# Display.net
KiCad netlist of a schematic drawn in EAGLE
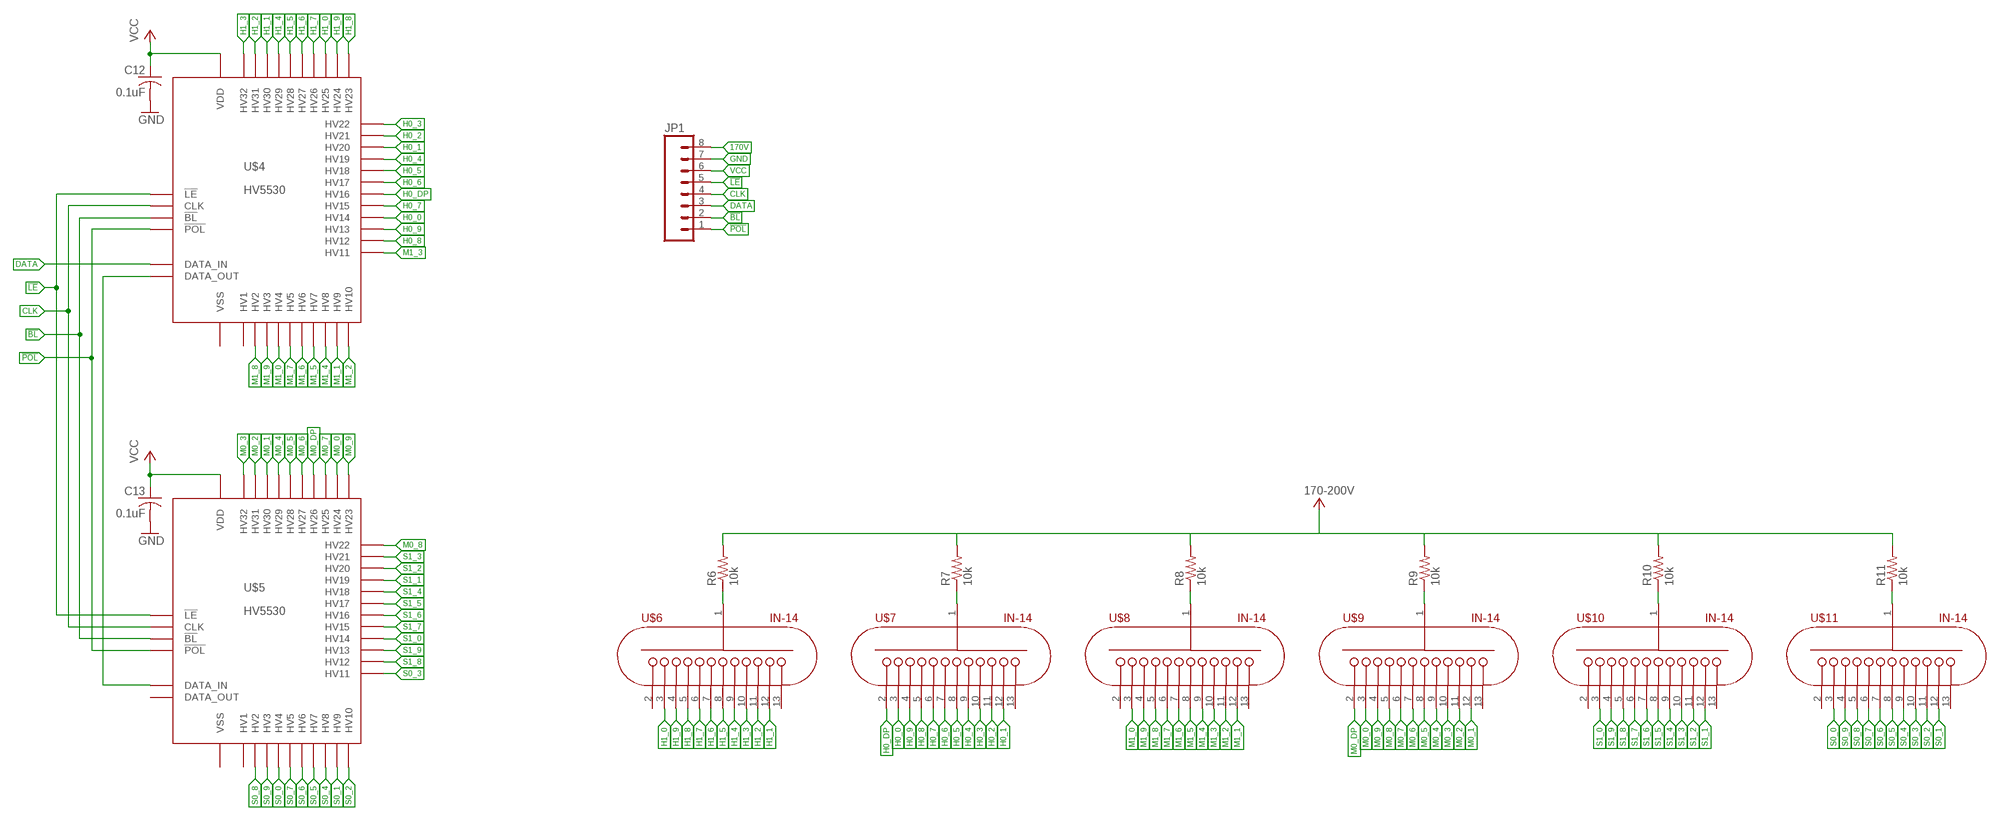
[diagram p0: schematic, sheet 1]

(export (version "E")
  (design (tool "Eeschema 10.0.6"))
  (components
    (comp (ref "C12")
      (value "0.1uF")
      (footprint "eagle-import:C0603")
      (libsource (lib "eagle-import") (part "C-USC0603"))
    )
    (comp (ref "C13")
      (value "0.1uF")
      (footprint "eagle-import:C0603")
      (libsource (lib "eagle-import") (part "C-USC0603"))
    )
    (comp (ref "JP1")
      (value "M08")
      (footprint "eagle-import:1X08_PIN1_NO_SILK")
      (libsource (lib "eagle-import") (part "M08"))
    )
    (comp (ref "R6")
      (value "10k")
      (footprint "eagle-import:R0603")
      (libsource (lib "eagle-import") (part "R-US_R0603"))
    )
    (comp (ref "R7")
      (value "10k")
      (footprint "eagle-import:R0603")
      (libsource (lib "eagle-import") (part "R-US_R0603"))
    )
    (comp (ref "R8")
      (value "10k")
      (footprint "eagle-import:R0603")
      (libsource (lib "eagle-import") (part "R-US_R0603"))
    )
    (comp (ref "R9")
      (value "10k")
      (footprint "eagle-import:R0603")
      (libsource (lib "eagle-import") (part "R-US_R0603"))
    )
    (comp (ref "R10")
      (value "10k")
      (footprint "eagle-import:R0603")
      (libsource (lib "eagle-import") (part "R-US_R0603"))
    )
    (comp (ref "R11")
      (value "10k")
      (footprint "eagle-import:R0603")
      (libsource (lib "eagle-import") (part "R-US_R0603"))
    )
    (comp (ref "U$4")
      (value "HV5530PLCC")
      (footprint "eagle-import:PLCC")
      (libsource (lib "eagle-import") (part "HV5530PLCC"))
    )
    (comp (ref "U$5")
      (value "HV5530PLCC")
      (footprint "eagle-import:PLCC")
      (libsource (lib "eagle-import") (part "HV5530PLCC"))
    )
    (comp (ref "U$6")
      (value "IN-14")
      (footprint "eagle-import:IN-14")
      (libsource (lib "eagle-import") (part "IN-14"))
    )
    (comp (ref "U$7")
      (value "IN-14")
      (footprint "eagle-import:IN-14")
      (libsource (lib "eagle-import") (part "IN-14"))
    )
    (comp (ref "U$8")
      (value "IN-14")
      (footprint "eagle-import:IN-14")
      (libsource (lib "eagle-import") (part "IN-14"))
    )
    (comp (ref "U$9")
      (value "IN-14")
      (footprint "eagle-import:IN-14")
      (libsource (lib "eagle-import") (part "IN-14"))
    )
    (comp (ref "U$10")
      (value "IN-14")
      (footprint "eagle-import:IN-14")
      (libsource (lib "eagle-import") (part "IN-14"))
    )
    (comp (ref "U$11")
      (value "IN-14")
      (footprint "eagle-import:IN-14")
      (libsource (lib "eagle-import") (part "IN-14"))
    )
  )
  (nets
    (net (code "1") (name "/~{BL}") (class "Default")
      (node (ref "JP1") (pin "2") (pinfunction "2_2") (pintype "passive"))
      (node (ref "U$4") (pin "BL") (pinfunction "~{BL}_BL") (pintype "bidirectional"))
      (node (ref "U$5") (pin "BL") (pinfunction "~{BL}_BL") (pintype "bidirectional"))
    )
    (net (code "2") (name "/~{LE}") (class "Default")
      (node (ref "JP1") (pin "5") (pinfunction "5_5") (pintype "passive"))
      (node (ref "U$4") (pin "LE") (pinfunction "~{LE}_LE") (pintype "bidirectional"))
      (node (ref "U$5") (pin "LE") (pinfunction "~{LE}_LE") (pintype "bidirectional"))
    )
    (net (code "3") (name "/~{POL}") (class "Default")
      (node (ref "JP1") (pin "1") (pinfunction "1_1") (pintype "passive"))
      (node (ref "U$4") (pin "POL") (pinfunction "~{POL}_POL") (pintype "bidirectional"))
      (node (ref "U$5") (pin "POL") (pinfunction "~{POL}_POL") (pintype "bidirectional"))
    )
    (net (code "4") (name "170V") (class "Default")
      (node (ref "JP1") (pin "8") (pinfunction "8_8") (pintype "passive"))
      (node (ref "R10") (pin "2") (pinfunction "2_2") (pintype "passive"))
      (node (ref "R11") (pin "2") (pinfunction "2_2") (pintype "passive"))
      (node (ref "R6") (pin "2") (pinfunction "2_2") (pintype "passive"))
      (node (ref "R7") (pin "2") (pinfunction "2_2") (pintype "passive"))
      (node (ref "R8") (pin "2") (pinfunction "2_2") (pintype "passive"))
      (node (ref "R9") (pin "2") (pinfunction "2_2") (pintype "passive"))
    )
    (net (code "5") (name "CLK") (class "Default")
      (node (ref "JP1") (pin "4") (pinfunction "4_4") (pintype "passive"))
      (node (ref "U$4") (pin "CLK") (pinfunction "CLK_CLK") (pintype "bidirectional"))
      (node (ref "U$5") (pin "CLK") (pinfunction "CLK_CLK") (pintype "bidirectional"))
    )
    (net (code "6") (name "DATA") (class "Default")
      (node (ref "JP1") (pin "3") (pinfunction "3_3") (pintype "passive"))
      (node (ref "U$4") (pin "D_IN") (pinfunction "DATA_IN_D_IN") (pintype "bidirectional"))
    )
    (net (code "7") (name "GND") (class "Default")
      (node (ref "C12") (pin "2") (pinfunction "2_2") (pintype "passive"))
      (node (ref "C13") (pin "2") (pinfunction "2_2") (pintype "passive"))
      (node (ref "JP1") (pin "7") (pinfunction "7_7") (pintype "passive"))
    )
    (net (code "8") (name "H0_0") (class "Default")
      (node (ref "U$4") (pin "HV14") (pinfunction "HV14_HV14") (pintype "bidirectional"))
      (node (ref "U$7") (pin "3") (pinfunction "P$3_3") (pintype "bidirectional"))
    )
    (net (code "9") (name "H0_1") (class "Default")
      (node (ref "U$4") (pin "HV20") (pinfunction "HV20_HV20") (pintype "bidirectional"))
      (node (ref "U$7") (pin "12") (pinfunction "P$12_12") (pintype "bidirectional"))
    )
    (net (code "10") (name "H0_2") (class "Default")
      (node (ref "U$4") (pin "HV21") (pinfunction "HV21_HV21") (pintype "bidirectional"))
      (node (ref "U$7") (pin "11") (pinfunction "P$11_11") (pintype "bidirectional"))
    )
    (net (code "11") (name "H0_3") (class "Default")
      (node (ref "U$4") (pin "HV22") (pinfunction "HV22_HV22") (pintype "bidirectional"))
      (node (ref "U$7") (pin "10") (pinfunction "P$10_10") (pintype "bidirectional"))
    )
    (net (code "12") (name "H0_4") (class "Default")
      (node (ref "U$4") (pin "HV19") (pinfunction "HV19_HV19") (pintype "bidirectional"))
      (node (ref "U$7") (pin "9") (pinfunction "P$9_9") (pintype "bidirectional"))
    )
    (net (code "13") (name "H0_5") (class "Default")
      (node (ref "U$4") (pin "HV18") (pinfunction "HV18_HV18") (pintype "bidirectional"))
      (node (ref "U$7") (pin "8") (pinfunction "P$8_8") (pintype "bidirectional"))
    )
    (net (code "14") (name "H0_6") (class "Default")
      (node (ref "U$4") (pin "HV17") (pinfunction "HV17_HV17") (pintype "bidirectional"))
      (node (ref "U$7") (pin "7") (pinfunction "P$7_7") (pintype "bidirectional"))
    )
    (net (code "15") (name "H0_7") (class "Default")
      (node (ref "U$4") (pin "HV15") (pinfunction "HV15_HV15") (pintype "bidirectional"))
      (node (ref "U$7") (pin "6") (pinfunction "P$6_6") (pintype "bidirectional"))
    )
    (net (code "16") (name "H0_8") (class "Default")
      (node (ref "U$4") (pin "HV12") (pinfunction "HV12_HV12") (pintype "bidirectional"))
      (node (ref "U$7") (pin "5") (pinfunction "P$5_5") (pintype "bidirectional"))
    )
    (net (code "17") (name "H0_9") (class "Default")
      (node (ref "U$4") (pin "HV13") (pinfunction "HV13_HV13") (pintype "bidirectional"))
      (node (ref "U$7") (pin "4") (pinfunction "P$4_4") (pintype "bidirectional"))
    )
    (net (code "18") (name "H0_DP") (class "Default")
      (node (ref "U$4") (pin "HV16") (pinfunction "HV16_HV16") (pintype "bidirectional"))
      (node (ref "U$7") (pin "2") (pinfunction "P$2_2") (pintype "bidirectional"))
    )
    (net (code "19") (name "H1_0") (class "Default")
      (node (ref "U$4") (pin "HV25") (pinfunction "HV25_HV25") (pintype "bidirectional"))
      (node (ref "U$6") (pin "3") (pinfunction "P$3_3") (pintype "bidirectional"))
    )
    (net (code "20") (name "H1_1") (class "Default")
      (node (ref "U$4") (pin "HV30") (pinfunction "HV30_HV30") (pintype "bidirectional"))
      (node (ref "U$6") (pin "12") (pinfunction "P$12_12") (pintype "bidirectional"))
    )
    (net (code "21") (name "H1_2") (class "Default")
      (node (ref "U$4") (pin "HV31") (pinfunction "HV31_HV31") (pintype "bidirectional"))
      (node (ref "U$6") (pin "11") (pinfunction "P$11_11") (pintype "bidirectional"))
    )
    (net (code "22") (name "H1_3") (class "Default")
      (node (ref "U$4") (pin "HV32") (pinfunction "HV32_HV32") (pintype "bidirectional"))
      (node (ref "U$6") (pin "10") (pinfunction "P$10_10") (pintype "bidirectional"))
    )
    (net (code "23") (name "H1_4") (class "Default")
      (node (ref "U$4") (pin "HV29") (pinfunction "HV29_HV29") (pintype "bidirectional"))
      (node (ref "U$6") (pin "9") (pinfunction "P$9_9") (pintype "bidirectional"))
    )
    (net (code "24") (name "H1_5") (class "Default")
      (node (ref "U$4") (pin "HV28") (pinfunction "HV28_HV28") (pintype "bidirectional"))
      (node (ref "U$6") (pin "8") (pinfunction "P$8_8") (pintype "bidirectional"))
    )
    (net (code "25") (name "H1_6") (class "Default")
      (node (ref "U$4") (pin "HV27") (pinfunction "HV27_HV27") (pintype "bidirectional"))
      (node (ref "U$6") (pin "7") (pinfunction "P$7_7") (pintype "bidirectional"))
    )
    (net (code "26") (name "H1_7") (class "Default")
      (node (ref "U$4") (pin "HV26") (pinfunction "HV26_HV26") (pintype "bidirectional"))
      (node (ref "U$6") (pin "6") (pinfunction "P$6_6") (pintype "bidirectional"))
    )
    (net (code "27") (name "H1_8") (class "Default")
      (node (ref "U$4") (pin "HV23") (pinfunction "HV23_HV23") (pintype "bidirectional"))
      (node (ref "U$6") (pin "5") (pinfunction "P$5_5") (pintype "bidirectional"))
    )
    (net (code "28") (name "H1_9") (class "Default")
      (node (ref "U$4") (pin "HV24") (pinfunction "HV24_HV24") (pintype "bidirectional"))
      (node (ref "U$6") (pin "4") (pinfunction "P$4_4") (pintype "bidirectional"))
    )
    (net (code "29") (name "M0_0") (class "Default")
      (node (ref "U$5") (pin "HV24") (pinfunction "HV24_HV24") (pintype "bidirectional"))
      (node (ref "U$9") (pin "3") (pinfunction "P$3_3") (pintype "bidirectional"))
    )
    (net (code "30") (name "M0_1") (class "Default")
      (node (ref "U$5") (pin "HV30") (pinfunction "HV30_HV30") (pintype "bidirectional"))
      (node (ref "U$9") (pin "12") (pinfunction "P$12_12") (pintype "bidirectional"))
    )
    (net (code "31") (name "M0_2") (class "Default")
      (node (ref "U$5") (pin "HV31") (pinfunction "HV31_HV31") (pintype "bidirectional"))
      (node (ref "U$9") (pin "11") (pinfunction "P$11_11") (pintype "bidirectional"))
    )
    (net (code "32") (name "M0_3") (class "Default")
      (node (ref "U$5") (pin "HV32") (pinfunction "HV32_HV32") (pintype "bidirectional"))
      (node (ref "U$9") (pin "10") (pinfunction "P$10_10") (pintype "bidirectional"))
    )
    (net (code "33") (name "M0_4") (class "Default")
      (node (ref "U$5") (pin "HV29") (pinfunction "HV29_HV29") (pintype "bidirectional"))
      (node (ref "U$9") (pin "9") (pinfunction "P$9_9") (pintype "bidirectional"))
    )
    (net (code "34") (name "M0_5") (class "Default")
      (node (ref "U$5") (pin "HV28") (pinfunction "HV28_HV28") (pintype "bidirectional"))
      (node (ref "U$9") (pin "8") (pinfunction "P$8_8") (pintype "bidirectional"))
    )
    (net (code "35") (name "M0_6") (class "Default")
      (node (ref "U$5") (pin "HV27") (pinfunction "HV27_HV27") (pintype "bidirectional"))
      (node (ref "U$9") (pin "7") (pinfunction "P$7_7") (pintype "bidirectional"))
    )
    (net (code "36") (name "M0_7") (class "Default")
      (node (ref "U$5") (pin "HV25") (pinfunction "HV25_HV25") (pintype "bidirectional"))
      (node (ref "U$9") (pin "6") (pinfunction "P$6_6") (pintype "bidirectional"))
    )
    (net (code "37") (name "M0_8") (class "Default")
      (node (ref "U$5") (pin "HV22") (pinfunction "HV22_HV22") (pintype "bidirectional"))
      (node (ref "U$9") (pin "5") (pinfunction "P$5_5") (pintype "bidirectional"))
    )
    (net (code "38") (name "M0_9") (class "Default")
      (node (ref "U$5") (pin "HV23") (pinfunction "HV23_HV23") (pintype "bidirectional"))
      (node (ref "U$9") (pin "4") (pinfunction "P$4_4") (pintype "bidirectional"))
    )
    (net (code "39") (name "M0_DP") (class "Default")
      (node (ref "U$5") (pin "HV26") (pinfunction "HV26_HV26") (pintype "bidirectional"))
      (node (ref "U$9") (pin "2") (pinfunction "P$2_2") (pintype "bidirectional"))
    )
    (net (code "40") (name "M1_0") (class "Default")
      (node (ref "U$4") (pin "HV4") (pinfunction "HV4_HV4") (pintype "bidirectional"))
      (node (ref "U$8") (pin "3") (pinfunction "P$3_3") (pintype "bidirectional"))
    )
    (net (code "41") (name "M1_1") (class "Default")
      (node (ref "U$4") (pin "HV9") (pinfunction "HV9_HV9") (pintype "bidirectional"))
      (node (ref "U$8") (pin "12") (pinfunction "P$12_12") (pintype "bidirectional"))
    )
    (net (code "42") (name "M1_2") (class "Default")
      (node (ref "U$4") (pin "HV10") (pinfunction "HV10_HV10") (pintype "bidirectional"))
      (node (ref "U$8") (pin "11") (pinfunction "P$11_11") (pintype "bidirectional"))
    )
    (net (code "43") (name "M1_3") (class "Default")
      (node (ref "U$4") (pin "HV11") (pinfunction "HV11_HV11") (pintype "bidirectional"))
      (node (ref "U$8") (pin "10") (pinfunction "P$10_10") (pintype "bidirectional"))
    )
    (net (code "44") (name "M1_4") (class "Default")
      (node (ref "U$4") (pin "HV8") (pinfunction "HV8_HV8") (pintype "bidirectional"))
      (node (ref "U$8") (pin "9") (pinfunction "P$9_9") (pintype "bidirectional"))
    )
    (net (code "45") (name "M1_5") (class "Default")
      (node (ref "U$4") (pin "HV7") (pinfunction "HV7_HV7") (pintype "bidirectional"))
      (node (ref "U$8") (pin "8") (pinfunction "P$8_8") (pintype "bidirectional"))
    )
    (net (code "46") (name "M1_6") (class "Default")
      (node (ref "U$4") (pin "HV6") (pinfunction "HV6_HV6") (pintype "bidirectional"))
      (node (ref "U$8") (pin "7") (pinfunction "P$7_7") (pintype "bidirectional"))
    )
    (net (code "47") (name "M1_7") (class "Default")
      (node (ref "U$4") (pin "HV5") (pinfunction "HV5_HV5") (pintype "bidirectional"))
      (node (ref "U$8") (pin "6") (pinfunction "P$6_6") (pintype "bidirectional"))
    )
    (net (code "48") (name "M1_8") (class "Default")
      (node (ref "U$4") (pin "HV2") (pinfunction "HV2_HV2") (pintype "bidirectional"))
      (node (ref "U$8") (pin "5") (pinfunction "P$5_5") (pintype "bidirectional"))
    )
    (net (code "49") (name "M1_9") (class "Default")
      (node (ref "U$4") (pin "HV3") (pinfunction "HV3_HV3") (pintype "bidirectional"))
      (node (ref "U$8") (pin "4") (pinfunction "P$4_4") (pintype "bidirectional"))
    )
    (net (code "50") (name "Net-(U$4-DATA_OUT)") (class "Default")
      (node (ref "U$4") (pin "D_OUT") (pinfunction "DATA_OUT_D_OUT") (pintype "bidirectional"))
      (node (ref "U$5") (pin "D_IN") (pinfunction "DATA_IN_D_IN") (pintype "bidirectional"))
    )
    (net (code "51") (name "Net-(U$6-P$1)") (class "Default")
      (node (ref "R6") (pin "1") (pinfunction "1_1") (pintype "passive"))
      (node (ref "U$6") (pin "1") (pinfunction "P$1_1") (pintype "power_in"))
    )
    (net (code "52") (name "Net-(U$7-P$1)") (class "Default")
      (node (ref "R7") (pin "1") (pinfunction "1_1") (pintype "passive"))
      (node (ref "U$7") (pin "1") (pinfunction "P$1_1") (pintype "power_in"))
    )
    (net (code "53") (name "Net-(U$8-P$1)") (class "Default")
      (node (ref "R8") (pin "1") (pinfunction "1_1") (pintype "passive"))
      (node (ref "U$8") (pin "1") (pinfunction "P$1_1") (pintype "power_in"))
    )
    (net (code "54") (name "Net-(U$9-P$1)") (class "Default")
      (node (ref "R9") (pin "1") (pinfunction "1_1") (pintype "passive"))
      (node (ref "U$9") (pin "1") (pinfunction "P$1_1") (pintype "power_in"))
    )
    (net (code "55") (name "Net-(U$10-P$1)") (class "Default")
      (node (ref "R10") (pin "1") (pinfunction "1_1") (pintype "passive"))
      (node (ref "U$10") (pin "1") (pinfunction "P$1_1") (pintype "power_in"))
    )
    (net (code "56") (name "Net-(U$11-P$1)") (class "Default")
      (node (ref "R11") (pin "1") (pinfunction "1_1") (pintype "passive"))
      (node (ref "U$11") (pin "1") (pinfunction "P$1_1") (pintype "power_in"))
    )
    (net (code "57") (name "S0_0") (class "Default")
      (node (ref "U$11") (pin "3") (pinfunction "P$3_3") (pintype "bidirectional"))
      (node (ref "U$5") (pin "HV4") (pinfunction "HV4_HV4") (pintype "bidirectional"))
    )
    (net (code "58") (name "S0_1") (class "Default")
      (node (ref "U$11") (pin "12") (pinfunction "P$12_12") (pintype "bidirectional"))
      (node (ref "U$5") (pin "HV9") (pinfunction "HV9_HV9") (pintype "bidirectional"))
    )
    (net (code "59") (name "S0_2") (class "Default")
      (node (ref "U$11") (pin "11") (pinfunction "P$11_11") (pintype "bidirectional"))
      (node (ref "U$5") (pin "HV10") (pinfunction "HV10_HV10") (pintype "bidirectional"))
    )
    (net (code "60") (name "S0_3") (class "Default")
      (node (ref "U$11") (pin "10") (pinfunction "P$10_10") (pintype "bidirectional"))
      (node (ref "U$5") (pin "HV11") (pinfunction "HV11_HV11") (pintype "bidirectional"))
    )
    (net (code "61") (name "S0_4") (class "Default")
      (node (ref "U$11") (pin "9") (pinfunction "P$9_9") (pintype "bidirectional"))
      (node (ref "U$5") (pin "HV8") (pinfunction "HV8_HV8") (pintype "bidirectional"))
    )
    (net (code "62") (name "S0_5") (class "Default")
      (node (ref "U$11") (pin "8") (pinfunction "P$8_8") (pintype "bidirectional"))
      (node (ref "U$5") (pin "HV7") (pinfunction "HV7_HV7") (pintype "bidirectional"))
    )
    (net (code "63") (name "S0_6") (class "Default")
      (node (ref "U$11") (pin "7") (pinfunction "P$7_7") (pintype "bidirectional"))
      (node (ref "U$5") (pin "HV6") (pinfunction "HV6_HV6") (pintype "bidirectional"))
    )
    (net (code "64") (name "S0_7") (class "Default")
      (node (ref "U$11") (pin "6") (pinfunction "P$6_6") (pintype "bidirectional"))
      (node (ref "U$5") (pin "HV5") (pinfunction "HV5_HV5") (pintype "bidirectional"))
    )
    (net (code "65") (name "S0_8") (class "Default")
      (node (ref "U$11") (pin "5") (pinfunction "P$5_5") (pintype "bidirectional"))
      (node (ref "U$5") (pin "HV2") (pinfunction "HV2_HV2") (pintype "bidirectional"))
    )
    (net (code "66") (name "S0_9") (class "Default")
      (node (ref "U$11") (pin "4") (pinfunction "P$4_4") (pintype "bidirectional"))
      (node (ref "U$5") (pin "HV3") (pinfunction "HV3_HV3") (pintype "bidirectional"))
    )
    (net (code "67") (name "S1_0") (class "Default")
      (node (ref "U$10") (pin "3") (pinfunction "P$3_3") (pintype "bidirectional"))
      (node (ref "U$5") (pin "HV14") (pinfunction "HV14_HV14") (pintype "bidirectional"))
    )
    (net (code "68") (name "S1_1") (class "Default")
      (node (ref "U$10") (pin "12") (pinfunction "P$12_12") (pintype "bidirectional"))
      (node (ref "U$5") (pin "HV19") (pinfunction "HV19_HV19") (pintype "bidirectional"))
    )
    (net (code "69") (name "S1_2") (class "Default")
      (node (ref "U$10") (pin "11") (pinfunction "P$11_11") (pintype "bidirectional"))
      (node (ref "U$5") (pin "HV20") (pinfunction "HV20_HV20") (pintype "bidirectional"))
    )
    (net (code "70") (name "S1_3") (class "Default")
      (node (ref "U$10") (pin "10") (pinfunction "P$10_10") (pintype "bidirectional"))
      (node (ref "U$5") (pin "HV21") (pinfunction "HV21_HV21") (pintype "bidirectional"))
    )
    (net (code "71") (name "S1_4") (class "Default")
      (node (ref "U$10") (pin "9") (pinfunction "P$9_9") (pintype "bidirectional"))
      (node (ref "U$5") (pin "HV18") (pinfunction "HV18_HV18") (pintype "bidirectional"))
    )
    (net (code "72") (name "S1_5") (class "Default")
      (node (ref "U$10") (pin "8") (pinfunction "P$8_8") (pintype "bidirectional"))
      (node (ref "U$5") (pin "HV17") (pinfunction "HV17_HV17") (pintype "bidirectional"))
    )
    (net (code "73") (name "S1_6") (class "Default")
      (node (ref "U$10") (pin "7") (pinfunction "P$7_7") (pintype "bidirectional"))
      (node (ref "U$5") (pin "HV16") (pinfunction "HV16_HV16") (pintype "bidirectional"))
    )
    (net (code "74") (name "S1_7") (class "Default")
      (node (ref "U$10") (pin "6") (pinfunction "P$6_6") (pintype "bidirectional"))
      (node (ref "U$5") (pin "HV15") (pinfunction "HV15_HV15") (pintype "bidirectional"))
    )
    (net (code "75") (name "S1_8") (class "Default")
      (node (ref "U$10") (pin "5") (pinfunction "P$5_5") (pintype "bidirectional"))
      (node (ref "U$5") (pin "HV12") (pinfunction "HV12_HV12") (pintype "bidirectional"))
    )
    (net (code "76") (name "S1_9") (class "Default")
      (node (ref "U$10") (pin "4") (pinfunction "P$4_4") (pintype "bidirectional"))
      (node (ref "U$5") (pin "HV13") (pinfunction "HV13_HV13") (pintype "bidirectional"))
    )
    (net (code "77") (name "VCC") (class "Default")
      (node (ref "C12") (pin "1") (pinfunction "1_1") (pintype "passive"))
      (node (ref "C13") (pin "1") (pinfunction "1_1") (pintype "passive"))
      (node (ref "JP1") (pin "6") (pinfunction "6_6") (pintype "passive"))
      (node (ref "U$4") (pin "VDD") (pinfunction "VDD_VDD") (pintype "bidirectional"))
      (node (ref "U$5") (pin "VDD") (pinfunction "VDD_VDD") (pintype "bidirectional"))
    )
    (net (code "78") (name "unconnected-(U$4-PadHV1)") (class "Default")
      (node (ref "U$4") (pin "HV1") (pinfunction "HV1_HV1") (pintype "bidirectional"))
    )
    (net (code "79") (name "unconnected-(U$4-PadVSS)") (class "Default")
      (node (ref "U$4") (pin "VSS") (pinfunction "VSS_VSS") (pintype "bidirectional"))
    )
    (net (code "80") (name "unconnected-(U$5-DATA_OUT-PadD_OUT)") (class "Default")
      (node (ref "U$5") (pin "D_OUT") (pinfunction "DATA_OUT_D_OUT") (pintype "bidirectional"))
    )
    (net (code "81") (name "unconnected-(U$5-PadHV1)") (class "Default")
      (node (ref "U$5") (pin "HV1") (pinfunction "HV1_HV1") (pintype "bidirectional"))
    )
    (net (code "82") (name "unconnected-(U$5-PadVSS)") (class "Default")
      (node (ref "U$5") (pin "VSS") (pinfunction "VSS_VSS") (pintype "bidirectional"))
    )
    (net (code "83") (name "unconnected-(U$6-P$2-Pad2)") (class "Default")
      (node (ref "U$6") (pin "2") (pinfunction "P$2_2") (pintype "bidirectional"))
    )
    (net (code "84") (name "unconnected-(U$6-P$13-Pad13)") (class "Default")
      (node (ref "U$6") (pin "13") (pinfunction "P$13_13") (pintype "bidirectional"))
    )
    (net (code "85") (name "unconnected-(U$7-P$13-Pad13)") (class "Default")
      (node (ref "U$7") (pin "13") (pinfunction "P$13_13") (pintype "bidirectional"))
    )
    (net (code "86") (name "unconnected-(U$8-P$2-Pad2)") (class "Default")
      (node (ref "U$8") (pin "2") (pinfunction "P$2_2") (pintype "bidirectional"))
    )
    (net (code "87") (name "unconnected-(U$8-P$13-Pad13)") (class "Default")
      (node (ref "U$8") (pin "13") (pinfunction "P$13_13") (pintype "bidirectional"))
    )
    (net (code "88") (name "unconnected-(U$9-P$13-Pad13)") (class "Default")
      (node (ref "U$9") (pin "13") (pinfunction "P$13_13") (pintype "bidirectional"))
    )
    (net (code "89") (name "unconnected-(U$10-P$2-Pad2)") (class "Default")
      (node (ref "U$10") (pin "2") (pinfunction "P$2_2") (pintype "bidirectional"))
    )
    (net (code "90") (name "unconnected-(U$10-P$13-Pad13)") (class "Default")
      (node (ref "U$10") (pin "13") (pinfunction "P$13_13") (pintype "bidirectional"))
    )
    (net (code "91") (name "unconnected-(U$11-P$2-Pad2)") (class "Default")
      (node (ref "U$11") (pin "2") (pinfunction "P$2_2") (pintype "bidirectional"))
    )
    (net (code "92") (name "unconnected-(U$11-P$13-Pad13)") (class "Default")
      (node (ref "U$11") (pin "13") (pinfunction "P$13_13") (pintype "bidirectional"))
    )
  )
)
